# power_channel.net
KiCad netlist of a schematic drawn in Altium Designer
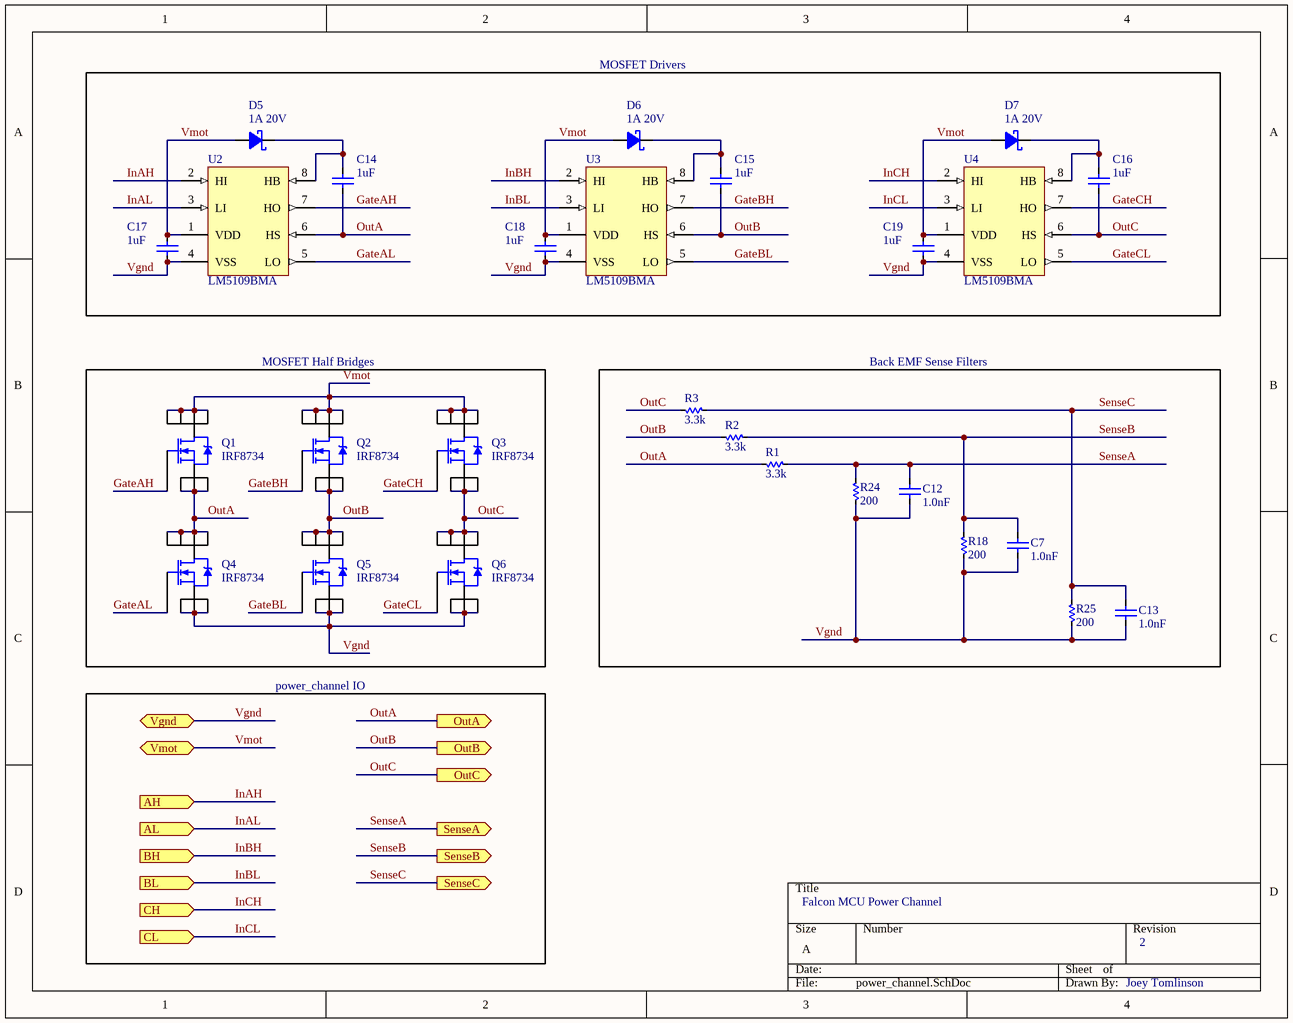
[diagram p0: power_channel.SchDoc]

(export (version "E")
  (design (tool "Eeschema 10.0.6"))
  (components
    (comp (ref "C7")
      (value "1.0nF")
      (footprint "0603 (1608)")
      (fields (field (name "PART NO.") "CC0603JRNPO8BN102") (field (name "Comment") "Capacitor"))
      (libsource (lib "SMT Chip") (part "Capacitor"))
    )
    (comp (ref "C12")
      (value "1.0nF")
      (footprint "0603 (1608)")
      (fields (field (name "PART NO.") "CC0603JRNPO8BN102") (field (name "Comment") "Capacitor"))
      (libsource (lib "SMT Chip") (part "Capacitor"))
    )
    (comp (ref "C13")
      (value "1.0nF")
      (footprint "0603 (1608)")
      (fields (field (name "PART NO.") "CC0603JRNPO8BN102") (field (name "Comment") "Capacitor"))
      (libsource (lib "SMT Chip") (part "Capacitor"))
    )
    (comp (ref "C14")
      (value "1uF")
      (footprint "0603 (1608)")
      (fields (field (name "PART NO.") "445-3452-1-ND") (field (name "Comment") "Capacitor"))
      (libsource (lib "SMT Chip") (part "Capacitor"))
    )
    (comp (ref "C15")
      (value "1uF")
      (footprint "0603 (1608)")
      (fields (field (name "PART NO.") "445-3452-1-ND") (field (name "Comment") "Capacitor"))
      (libsource (lib "SMT Chip") (part "Capacitor"))
    )
    (comp (ref "C16")
      (value "1uF")
      (footprint "0603 (1608)")
      (fields (field (name "PART NO.") "445-3452-1-ND") (field (name "Comment") "Capacitor"))
      (libsource (lib "SMT Chip") (part "Capacitor"))
    )
    (comp (ref "C17")
      (value "1uF")
      (footprint "0603 (1608)")
      (fields (field (name "PART NO.") "445-3452-1-ND") (field (name "Comment") "Capacitor"))
      (libsource (lib "SMT Chip") (part "Capacitor"))
    )
    (comp (ref "C18")
      (value "1uF")
      (footprint "0603 (1608)")
      (fields (field (name "PART NO.") "445-3452-1-ND") (field (name "Comment") "Capacitor"))
      (libsource (lib "SMT Chip") (part "Capacitor"))
    )
    (comp (ref "C19")
      (value "1uF")
      (footprint "0603 (1608)")
      (fields (field (name "PART NO.") "445-3452-1-ND") (field (name "Comment") "Capacitor"))
      (libsource (lib "SMT Chip") (part "Capacitor"))
    )
    (comp (ref "D5")
      (value "1A 20V")
      (footprint "SOD-323")
      (description "Schottky Diode")
      (fields (field (name "PART NO.") "SDM100K30LDICT-ND"))
      (libsource (lib "Diode") (part "Schottky Diode"))
    )
    (comp (ref "D6")
      (value "1A 20V")
      (footprint "SOD-323")
      (description "Schottky Diode")
      (fields (field (name "PART NO.") "SDM100K30LDICT-ND"))
      (libsource (lib "Diode") (part "Schottky Diode"))
    )
    (comp (ref "D7")
      (value "1A 20V")
      (footprint "SOD-323")
      (description "Schottky Diode")
      (fields (field (name "PART NO.") "SDM100K30LDICT-ND"))
      (libsource (lib "Diode") (part "Schottky Diode"))
    )
    (comp (ref "Q1")
      (value "IRF8734")
      (footprint "SO8")
      (fields (field (name "PART NO.") "IRF8734TRPBFCT-ND"))
      (libsource (lib "falcon") (part "IRF8734"))
    )
    (comp (ref "Q2")
      (value "IRF8734")
      (footprint "SO8")
      (fields (field (name "PART NO.") "IRF8734TRPBFCT-ND"))
      (libsource (lib "falcon") (part "IRF8734"))
    )
    (comp (ref "Q3")
      (value "IRF8734")
      (footprint "SO8")
      (fields (field (name "PART NO.") "IRF8734TRPBFCT-ND"))
      (libsource (lib "falcon") (part "IRF8734"))
    )
    (comp (ref "Q4")
      (value "IRF8734")
      (footprint "SO8")
      (fields (field (name "PART NO.") "IRF8734TRPBFCT-ND"))
      (libsource (lib "falcon") (part "IRF8734"))
    )
    (comp (ref "Q5")
      (value "IRF8734")
      (footprint "SO8")
      (fields (field (name "PART NO.") "IRF8734TRPBFCT-ND"))
      (libsource (lib "falcon") (part "IRF8734"))
    )
    (comp (ref "Q6")
      (value "IRF8734")
      (footprint "SO8")
      (fields (field (name "PART NO.") "IRF8734TRPBFCT-ND"))
      (libsource (lib "falcon") (part "IRF8734"))
    )
    (comp (ref "R1")
      (value "3.3k")
      (footprint "0603 (1608)")
      (description "Resistor")
      (fields (field (name "PART NO.") "RMCF0603JT3K30"))
      (libsource (lib "SMT Chip") (part "Resistor"))
    )
    (comp (ref "R2")
      (value "3.3k")
      (footprint "0603 (1608)")
      (description "Resistor")
      (fields (field (name "PART NO.") "RMCF0603JT3K30"))
      (libsource (lib "SMT Chip") (part "Resistor"))
    )
    (comp (ref "R3")
      (value "3.3k")
      (footprint "0603 (1608)")
      (description "Resistor")
      (fields (field (name "PART NO.") "RMCF0603JT3K30"))
      (libsource (lib "SMT Chip") (part "Resistor"))
    )
    (comp (ref "R18")
      (value "200")
      (footprint "0603 (1608)")
      (description "Resistor")
      (fields (field (name "PART NO.") "RMCF0603JT200R"))
      (libsource (lib "SMT Chip") (part "Resistor"))
    )
    (comp (ref "R24")
      (value "200")
      (footprint "0603 (1608)")
      (description "Resistor")
      (fields (field (name "PART NO.") "RMCF0603JT200R"))
      (libsource (lib "SMT Chip") (part "Resistor"))
    )
    (comp (ref "R25")
      (value "200")
      (footprint "0603 (1608)")
      (description "Resistor")
      (fields (field (name "PART NO.") "RMCF0603JT200R"))
      (libsource (lib "SMT Chip") (part "Resistor"))
    )
    (comp (ref "U2")
      (value "LM5109BMA")
      (footprint "M08A_N")
      (description "High Voltage 1A Peak Half Bridge Gate Driver")
      (fields
        (field (name "MANUFACTURER") "National Semiconductor")
        (field (name "DIGIKEYPARTNUMBER") "LM5109BMA-ND")
        (field (name "PUBLISHER") "Altium Limited")
      )
      (libsource (lib "NSC MiscPower") (part "LM5109BMA"))
    )
    (comp (ref "U3")
      (value "LM5109BMA")
      (footprint "M08A_N")
      (description "High Voltage 1A Peak Half Bridge Gate Driver")
      (fields
        (field (name "MANUFACTURER") "National Semiconductor")
        (field (name "DIGIKEYPARTNUMBER") "LM5109BMA-ND")
        (field (name "PUBLISHER") "Altium Limited")
      )
      (libsource (lib "NSC MiscPower") (part "LM5109BMA"))
    )
    (comp (ref "U4")
      (value "LM5109BMA")
      (footprint "M08A_N")
      (description "High Voltage 1A Peak Half Bridge Gate Driver")
      (fields
        (field (name "MANUFACTURER") "National Semiconductor")
        (field (name "DIGIKEYPARTNUMBER") "LM5109BMA-ND")
        (field (name "PUBLISHER") "Altium Limited")
      )
      (libsource (lib "NSC MiscPower") (part "LM5109BMA"))
    )
  )
  (nets
    (net (code "1") (name "/GateAH") (class "Default")
      (node (ref "Q1") (pin "4") (pinfunction "G_4") (pintype "passive"))
      (node (ref "U2") (pin "7") (pinfunction "HO_7") (pintype "output"))
    )
    (net (code "2") (name "/GateAL") (class "Default")
      (node (ref "Q4") (pin "4") (pinfunction "G_4") (pintype "passive"))
      (node (ref "U2") (pin "5") (pinfunction "LO_5") (pintype "output"))
    )
    (net (code "3") (name "/GateBH") (class "Default")
      (node (ref "Q2") (pin "4") (pinfunction "G_4") (pintype "passive"))
      (node (ref "U3") (pin "7") (pinfunction "HO_7") (pintype "output"))
    )
    (net (code "4") (name "/GateBL") (class "Default")
      (node (ref "Q5") (pin "4") (pinfunction "G_4") (pintype "passive"))
      (node (ref "U3") (pin "5") (pinfunction "LO_5") (pintype "output"))
    )
    (net (code "5") (name "/GateCH") (class "Default")
      (node (ref "Q3") (pin "4") (pinfunction "G_4") (pintype "passive"))
      (node (ref "U4") (pin "7") (pinfunction "HO_7") (pintype "output"))
    )
    (net (code "6") (name "/GateCL") (class "Default")
      (node (ref "Q6") (pin "4") (pinfunction "G_4") (pintype "passive"))
      (node (ref "U4") (pin "5") (pinfunction "LO_5") (pintype "output"))
    )
    (net (code "7") (name "/InAH") (class "Default")
      (node (ref "U2") (pin "2") (pinfunction "HI_2") (pintype "input"))
    )
    (net (code "8") (name "/InAL") (class "Default")
      (node (ref "U2") (pin "3") (pinfunction "LI_3") (pintype "input"))
    )
    (net (code "9") (name "/InBH") (class "Default")
      (node (ref "U3") (pin "2") (pinfunction "HI_2") (pintype "input"))
    )
    (net (code "10") (name "/InBL") (class "Default")
      (node (ref "U3") (pin "3") (pinfunction "LI_3") (pintype "input"))
    )
    (net (code "11") (name "/InCH") (class "Default")
      (node (ref "U4") (pin "2") (pinfunction "HI_2") (pintype "input"))
    )
    (net (code "12") (name "/InCL") (class "Default")
      (node (ref "U4") (pin "3") (pinfunction "LI_3") (pintype "input"))
    )
    (net (code "13") (name "/OutA") (class "Default")
      (node (ref "C14") (pin "2") (pinfunction "2_2") (pintype "passive"))
      (node (ref "Q1") (pin "1") (pinfunction "S_1") (pintype "passive"))
      (node (ref "Q1") (pin "2") (pinfunction "S_2") (pintype "passive"))
      (node (ref "Q1") (pin "3") (pinfunction "S_3") (pintype "passive"))
      (node (ref "Q4") (pin "5") (pinfunction "D_5") (pintype "passive"))
      (node (ref "Q4") (pin "6") (pinfunction "D_6") (pintype "passive"))
      (node (ref "Q4") (pin "7") (pinfunction "D_7") (pintype "passive"))
      (node (ref "Q4") (pin "8") (pinfunction "D_8") (pintype "passive"))
      (node (ref "R1") (pin "2") (pinfunction "2_2") (pintype "passive"))
      (node (ref "U2") (pin "6") (pinfunction "HS_6") (pintype "input"))
    )
    (net (code "14") (name "/OutB") (class "Default")
      (node (ref "C15") (pin "2") (pinfunction "2_2") (pintype "passive"))
      (node (ref "Q2") (pin "1") (pinfunction "S_1") (pintype "passive"))
      (node (ref "Q2") (pin "2") (pinfunction "S_2") (pintype "passive"))
      (node (ref "Q2") (pin "3") (pinfunction "S_3") (pintype "passive"))
      (node (ref "Q5") (pin "5") (pinfunction "D_5") (pintype "passive"))
      (node (ref "Q5") (pin "6") (pinfunction "D_6") (pintype "passive"))
      (node (ref "Q5") (pin "7") (pinfunction "D_7") (pintype "passive"))
      (node (ref "Q5") (pin "8") (pinfunction "D_8") (pintype "passive"))
      (node (ref "R2") (pin "2") (pinfunction "2_2") (pintype "passive"))
      (node (ref "U3") (pin "6") (pinfunction "HS_6") (pintype "input"))
    )
    (net (code "15") (name "/OutC") (class "Default")
      (node (ref "C16") (pin "2") (pinfunction "2_2") (pintype "passive"))
      (node (ref "Q3") (pin "1") (pinfunction "S_1") (pintype "passive"))
      (node (ref "Q3") (pin "2") (pinfunction "S_2") (pintype "passive"))
      (node (ref "Q3") (pin "3") (pinfunction "S_3") (pintype "passive"))
      (node (ref "Q6") (pin "5") (pinfunction "D_5") (pintype "passive"))
      (node (ref "Q6") (pin "6") (pinfunction "D_6") (pintype "passive"))
      (node (ref "Q6") (pin "7") (pinfunction "D_7") (pintype "passive"))
      (node (ref "Q6") (pin "8") (pinfunction "D_8") (pintype "passive"))
      (node (ref "R3") (pin "2") (pinfunction "2_2") (pintype "passive"))
      (node (ref "U4") (pin "6") (pinfunction "HS_6") (pintype "input"))
    )
    (net (code "16") (name "/SenseA") (class "Default")
      (node (ref "C12") (pin "1") (pinfunction "1_1") (pintype "passive"))
      (node (ref "R1") (pin "1") (pinfunction "1_1") (pintype "passive"))
      (node (ref "R24") (pin "1") (pinfunction "1_1") (pintype "passive"))
    )
    (net (code "17") (name "/SenseB") (class "Default")
      (node (ref "C7") (pin "1") (pinfunction "1_1") (pintype "passive"))
      (node (ref "R18") (pin "1") (pinfunction "1_1") (pintype "passive"))
      (node (ref "R2") (pin "1") (pinfunction "1_1") (pintype "passive"))
    )
    (net (code "18") (name "/SenseC") (class "Default")
      (node (ref "C13") (pin "1") (pinfunction "1_1") (pintype "passive"))
      (node (ref "R25") (pin "1") (pinfunction "1_1") (pintype "passive"))
      (node (ref "R3") (pin "1") (pinfunction "1_1") (pintype "passive"))
    )
    (net (code "19") (name "/Vgnd") (class "Default")
      (node (ref "C12") (pin "2") (pinfunction "2_2") (pintype "passive"))
      (node (ref "C13") (pin "2") (pinfunction "2_2") (pintype "passive"))
      (node (ref "C17") (pin "2") (pinfunction "2_2") (pintype "passive"))
      (node (ref "C18") (pin "2") (pinfunction "2_2") (pintype "passive"))
      (node (ref "C19") (pin "2") (pinfunction "2_2") (pintype "passive"))
      (node (ref "C7") (pin "2") (pinfunction "2_2") (pintype "passive"))
      (node (ref "Q4") (pin "1") (pinfunction "S_1") (pintype "passive"))
      (node (ref "Q4") (pin "2") (pinfunction "S_2") (pintype "passive"))
      (node (ref "Q4") (pin "3") (pinfunction "S_3") (pintype "passive"))
      (node (ref "Q5") (pin "1") (pinfunction "S_1") (pintype "passive"))
      (node (ref "Q5") (pin "2") (pinfunction "S_2") (pintype "passive"))
      (node (ref "Q5") (pin "3") (pinfunction "S_3") (pintype "passive"))
      (node (ref "Q6") (pin "1") (pinfunction "S_1") (pintype "passive"))
      (node (ref "Q6") (pin "2") (pinfunction "S_2") (pintype "passive"))
      (node (ref "Q6") (pin "3") (pinfunction "S_3") (pintype "passive"))
      (node (ref "R18") (pin "2") (pinfunction "2_2") (pintype "passive"))
      (node (ref "R24") (pin "2") (pinfunction "2_2") (pintype "passive"))
      (node (ref "R25") (pin "2") (pinfunction "2_2") (pintype "passive"))
      (node (ref "U2") (pin "4") (pinfunction "VSS_4") (pintype "power_in"))
      (node (ref "U3") (pin "4") (pinfunction "VSS_4") (pintype "power_in"))
      (node (ref "U4") (pin "4") (pinfunction "VSS_4") (pintype "power_in"))
    )
    (net (code "20") (name "/Vmot") (class "Default")
      (node (ref "C17") (pin "1") (pinfunction "1_1") (pintype "passive"))
      (node (ref "C18") (pin "1") (pinfunction "1_1") (pintype "passive"))
      (node (ref "C19") (pin "1") (pinfunction "1_1") (pintype "passive"))
      (node (ref "D5") (pin "1") (pinfunction "1_1") (pintype "passive"))
      (node (ref "D6") (pin "1") (pinfunction "1_1") (pintype "passive"))
      (node (ref "D7") (pin "1") (pinfunction "1_1") (pintype "passive"))
      (node (ref "Q1") (pin "5") (pinfunction "D_5") (pintype "passive"))
      (node (ref "Q1") (pin "6") (pinfunction "D_6") (pintype "passive"))
      (node (ref "Q1") (pin "7") (pinfunction "D_7") (pintype "passive"))
      (node (ref "Q1") (pin "8") (pinfunction "D_8") (pintype "passive"))
      (node (ref "Q2") (pin "5") (pinfunction "D_5") (pintype "passive"))
      (node (ref "Q2") (pin "6") (pinfunction "D_6") (pintype "passive"))
      (node (ref "Q2") (pin "7") (pinfunction "D_7") (pintype "passive"))
      (node (ref "Q2") (pin "8") (pinfunction "D_8") (pintype "passive"))
      (node (ref "Q3") (pin "5") (pinfunction "D_5") (pintype "passive"))
      (node (ref "Q3") (pin "6") (pinfunction "D_6") (pintype "passive"))
      (node (ref "Q3") (pin "7") (pinfunction "D_7") (pintype "passive"))
      (node (ref "Q3") (pin "8") (pinfunction "D_8") (pintype "passive"))
      (node (ref "U2") (pin "1") (pinfunction "VDD_1") (pintype "power_in"))
      (node (ref "U3") (pin "1") (pinfunction "VDD_1") (pintype "power_in"))
      (node (ref "U4") (pin "1") (pinfunction "VDD_1") (pintype "power_in"))
    )
    (net (code "21") (name "Net-(U2-HB)") (class "Default")
      (node (ref "C14") (pin "1") (pinfunction "1_1") (pintype "passive"))
      (node (ref "D5") (pin "2") (pinfunction "2_2") (pintype "passive"))
      (node (ref "U2") (pin "8") (pinfunction "HB_8") (pintype "input"))
    )
    (net (code "22") (name "Net-(U3-HB)") (class "Default")
      (node (ref "C15") (pin "1") (pinfunction "1_1") (pintype "passive"))
      (node (ref "D6") (pin "2") (pinfunction "2_2") (pintype "passive"))
      (node (ref "U3") (pin "8") (pinfunction "HB_8") (pintype "input"))
    )
    (net (code "23") (name "Net-(U4-HB)") (class "Default")
      (node (ref "C16") (pin "1") (pinfunction "1_1") (pintype "passive"))
      (node (ref "D7") (pin "2") (pinfunction "2_2") (pintype "passive"))
      (node (ref "U4") (pin "8") (pinfunction "HB_8") (pintype "input"))
    )
  )
)
